# Third_try-following_diagram.net
KiCad netlist of a schematic drawn in EAGLE
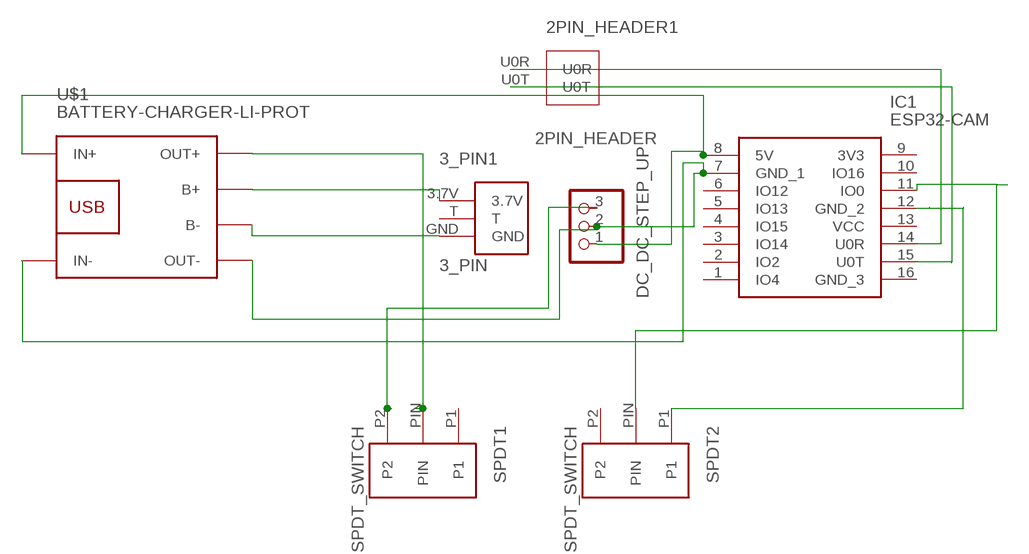
[diagram p0: schematic, sheet 1]

(export (version "E")
  (design (tool "Eeschema 10.0.6"))
  (components
    (comp (ref "2PIN_HEADER1")
      (value "2PIN_HEADER")
      (footprint "eagle-import:2PIN_HEADER")
      (libsource (lib "eagle-import") (part "2PIN_HEADER"))
    )
    (comp (ref "3_PIN1")
      (value "3_PIN")
      (footprint "eagle-import:3_PIN")
      (libsource (lib "eagle-import") (part "3_PIN"))
    )
    (comp (ref "DC_DC_STEP_UP")
      (value "PINHD-1X3")
      (footprint "eagle-import:1X03")
      (libsource (lib "eagle-import") (part "PINHD-1X3"))
    )
    (comp (ref "IC1")
      (value "ESP32-CAM")
      (footprint "eagle-import:ESP32CAM")
      (libsource (lib "eagle-import") (part "ESP32-CAM"))
    )
    (comp (ref "SPDT1")
      (value "SPDT_SWITCH")
      (footprint "eagle-import:SPDT_SWITCH")
      (libsource (lib "eagle-import") (part "SPDT_SWITCH"))
    )
    (comp (ref "SPDT2")
      (value "SPDT_SWITCH")
      (footprint "eagle-import:SPDT_SWITCH")
      (libsource (lib "eagle-import") (part "SPDT_SWITCH"))
    )
    (comp (ref "U$1")
      (value "BATTERY-CHARGER-LI-PROT")
      (footprint "eagle-import:BATTERY-CHARGER-LI-PROT")
      (libsource (lib "eagle-import") (part "BATTERY-CHARGER-LI-PROT"))
    )
  )
  (nets
    (net (code "1") (name "Net-(3_PIN1-Pad3.7V)") (class "Default")
      (node (ref "3_PIN1") (pin "3.7V") (pinfunction "3.7V_3.7V") (pintype "bidirectional"))
      (node (ref "U$1") (pin "B+") (pinfunction "B+_B+") (pintype "bidirectional"))
    )
    (net (code "2") (name "Net-(3_PIN1-PadGND)") (class "Default")
      (node (ref "3_PIN1") (pin "GND") (pinfunction "GND_GND") (pintype "bidirectional"))
      (node (ref "U$1") (pin "B-") (pinfunction "B-_B-") (pintype "bidirectional"))
    )
    (net (code "3") (name "Net-(DC_DC_STEP_UP-Pad3)") (class "Default")
      (node (ref "DC_DC_STEP_UP") (pin "3") (pinfunction "3_3") (pintype "passive"))
      (node (ref "SPDT1") (pin "P2") (pinfunction "P2_P2") (pintype "bidirectional"))
    )
    (net (code "4") (name "Net-(IC1-5V)") (class "Default")
      (node (ref "DC_DC_STEP_UP") (pin "1") (pinfunction "1_1") (pintype "passive"))
      (node (ref "IC1") (pin "8") (pinfunction "5V_8") (pintype "bidirectional"))
      (node (ref "U$1") (pin "IN+") (pinfunction "IN+_IN+") (pintype "bidirectional"))
    )
    (net (code "5") (name "Net-(IC1-GND_1)") (class "Default")
      (node (ref "DC_DC_STEP_UP") (pin "2") (pinfunction "2_2") (pintype "passive"))
      (node (ref "IC1") (pin "7") (pinfunction "GND_1_7") (pintype "bidirectional"))
      (node (ref "U$1") (pin "IN-") (pinfunction "IN-_IN-") (pintype "bidirectional"))
      (node (ref "U$1") (pin "OUT-") (pinfunction "OUT-_OUT-") (pintype "bidirectional"))
    )
    (net (code "6") (name "Net-(IC1-GND_2)") (class "Default")
      (node (ref "IC1") (pin "12") (pinfunction "GND_2_12") (pintype "bidirectional"))
      (node (ref "SPDT2") (pin "P1") (pinfunction "P1_P1") (pintype "bidirectional"))
    )
    (net (code "7") (name "Net-(IC1-IO0)") (class "Default")
      (node (ref "IC1") (pin "11") (pinfunction "IO0_11") (pintype "bidirectional"))
      (node (ref "SPDT2") (pin "PIN") (pinfunction "PIN_PIN") (pintype "bidirectional"))
    )
    (net (code "8") (name "Net-(IC1-U0R)") (class "Default")
      (node (ref "2PIN_HEADER1") (pin "U0R") (pinfunction "U0R_U0R") (pintype "bidirectional"))
      (node (ref "IC1") (pin "14") (pinfunction "U0R_14") (pintype "bidirectional"))
    )
    (net (code "9") (name "Net-(IC1-U0T)") (class "Default")
      (node (ref "2PIN_HEADER1") (pin "U0T") (pinfunction "U0T_U0T") (pintype "bidirectional"))
      (node (ref "IC1") (pin "15") (pinfunction "U0T_15") (pintype "bidirectional"))
    )
    (net (code "10") (name "Net-(SPDT1-PadPIN)") (class "Default")
      (node (ref "SPDT1") (pin "PIN") (pinfunction "PIN_PIN") (pintype "bidirectional"))
      (node (ref "U$1") (pin "OUT+") (pinfunction "OUT+_OUT+") (pintype "bidirectional"))
    )
    (net (code "11") (name "unconnected-(3_PIN1-PadT)") (class "Default")
      (node (ref "3_PIN1") (pin "T") (pinfunction "T_T") (pintype "bidirectional"))
    )
    (net (code "12") (name "unconnected-(IC1-3V3-Pad9)") (class "Default")
      (node (ref "IC1") (pin "9") (pinfunction "3V3_9") (pintype "bidirectional"))
    )
    (net (code "13") (name "unconnected-(IC1-GND_3-Pad16)") (class "Default")
      (node (ref "IC1") (pin "16") (pinfunction "GND_3_16") (pintype "bidirectional"))
    )
    (net (code "14") (name "unconnected-(IC1-IO2-Pad2)") (class "Default")
      (node (ref "IC1") (pin "2") (pinfunction "IO2_2") (pintype "bidirectional"))
    )
    (net (code "15") (name "unconnected-(IC1-IO4-Pad1)") (class "Default")
      (node (ref "IC1") (pin "1") (pinfunction "IO4_1") (pintype "bidirectional"))
    )
    (net (code "16") (name "unconnected-(IC1-IO12-Pad6)") (class "Default")
      (node (ref "IC1") (pin "6") (pinfunction "IO12_6") (pintype "bidirectional"))
    )
    (net (code "17") (name "unconnected-(IC1-IO13-Pad5)") (class "Default")
      (node (ref "IC1") (pin "5") (pinfunction "IO13_5") (pintype "bidirectional"))
    )
    (net (code "18") (name "unconnected-(IC1-IO14-Pad3)") (class "Default")
      (node (ref "IC1") (pin "3") (pinfunction "IO14_3") (pintype "bidirectional"))
    )
    (net (code "19") (name "unconnected-(IC1-IO15-Pad4)") (class "Default")
      (node (ref "IC1") (pin "4") (pinfunction "IO15_4") (pintype "bidirectional"))
    )
    (net (code "20") (name "unconnected-(IC1-IO16-Pad10)") (class "Default")
      (node (ref "IC1") (pin "10") (pinfunction "IO16_10") (pintype "bidirectional"))
    )
    (net (code "21") (name "unconnected-(IC1-VCC-Pad13)") (class "Default")
      (node (ref "IC1") (pin "13") (pinfunction "VCC_13") (pintype "bidirectional"))
    )
    (net (code "22") (name "unconnected-(SPDT1-PadP1)") (class "Default")
      (node (ref "SPDT1") (pin "P1") (pinfunction "P1_P1") (pintype "bidirectional"))
    )
    (net (code "23") (name "unconnected-(SPDT2-PadP2)") (class "Default")
      (node (ref "SPDT2") (pin "P2") (pinfunction "P2_P2") (pintype "bidirectional"))
    )
  )
)
